# Sheet2.net
KiCad netlist of a schematic drawn in Altium Designer
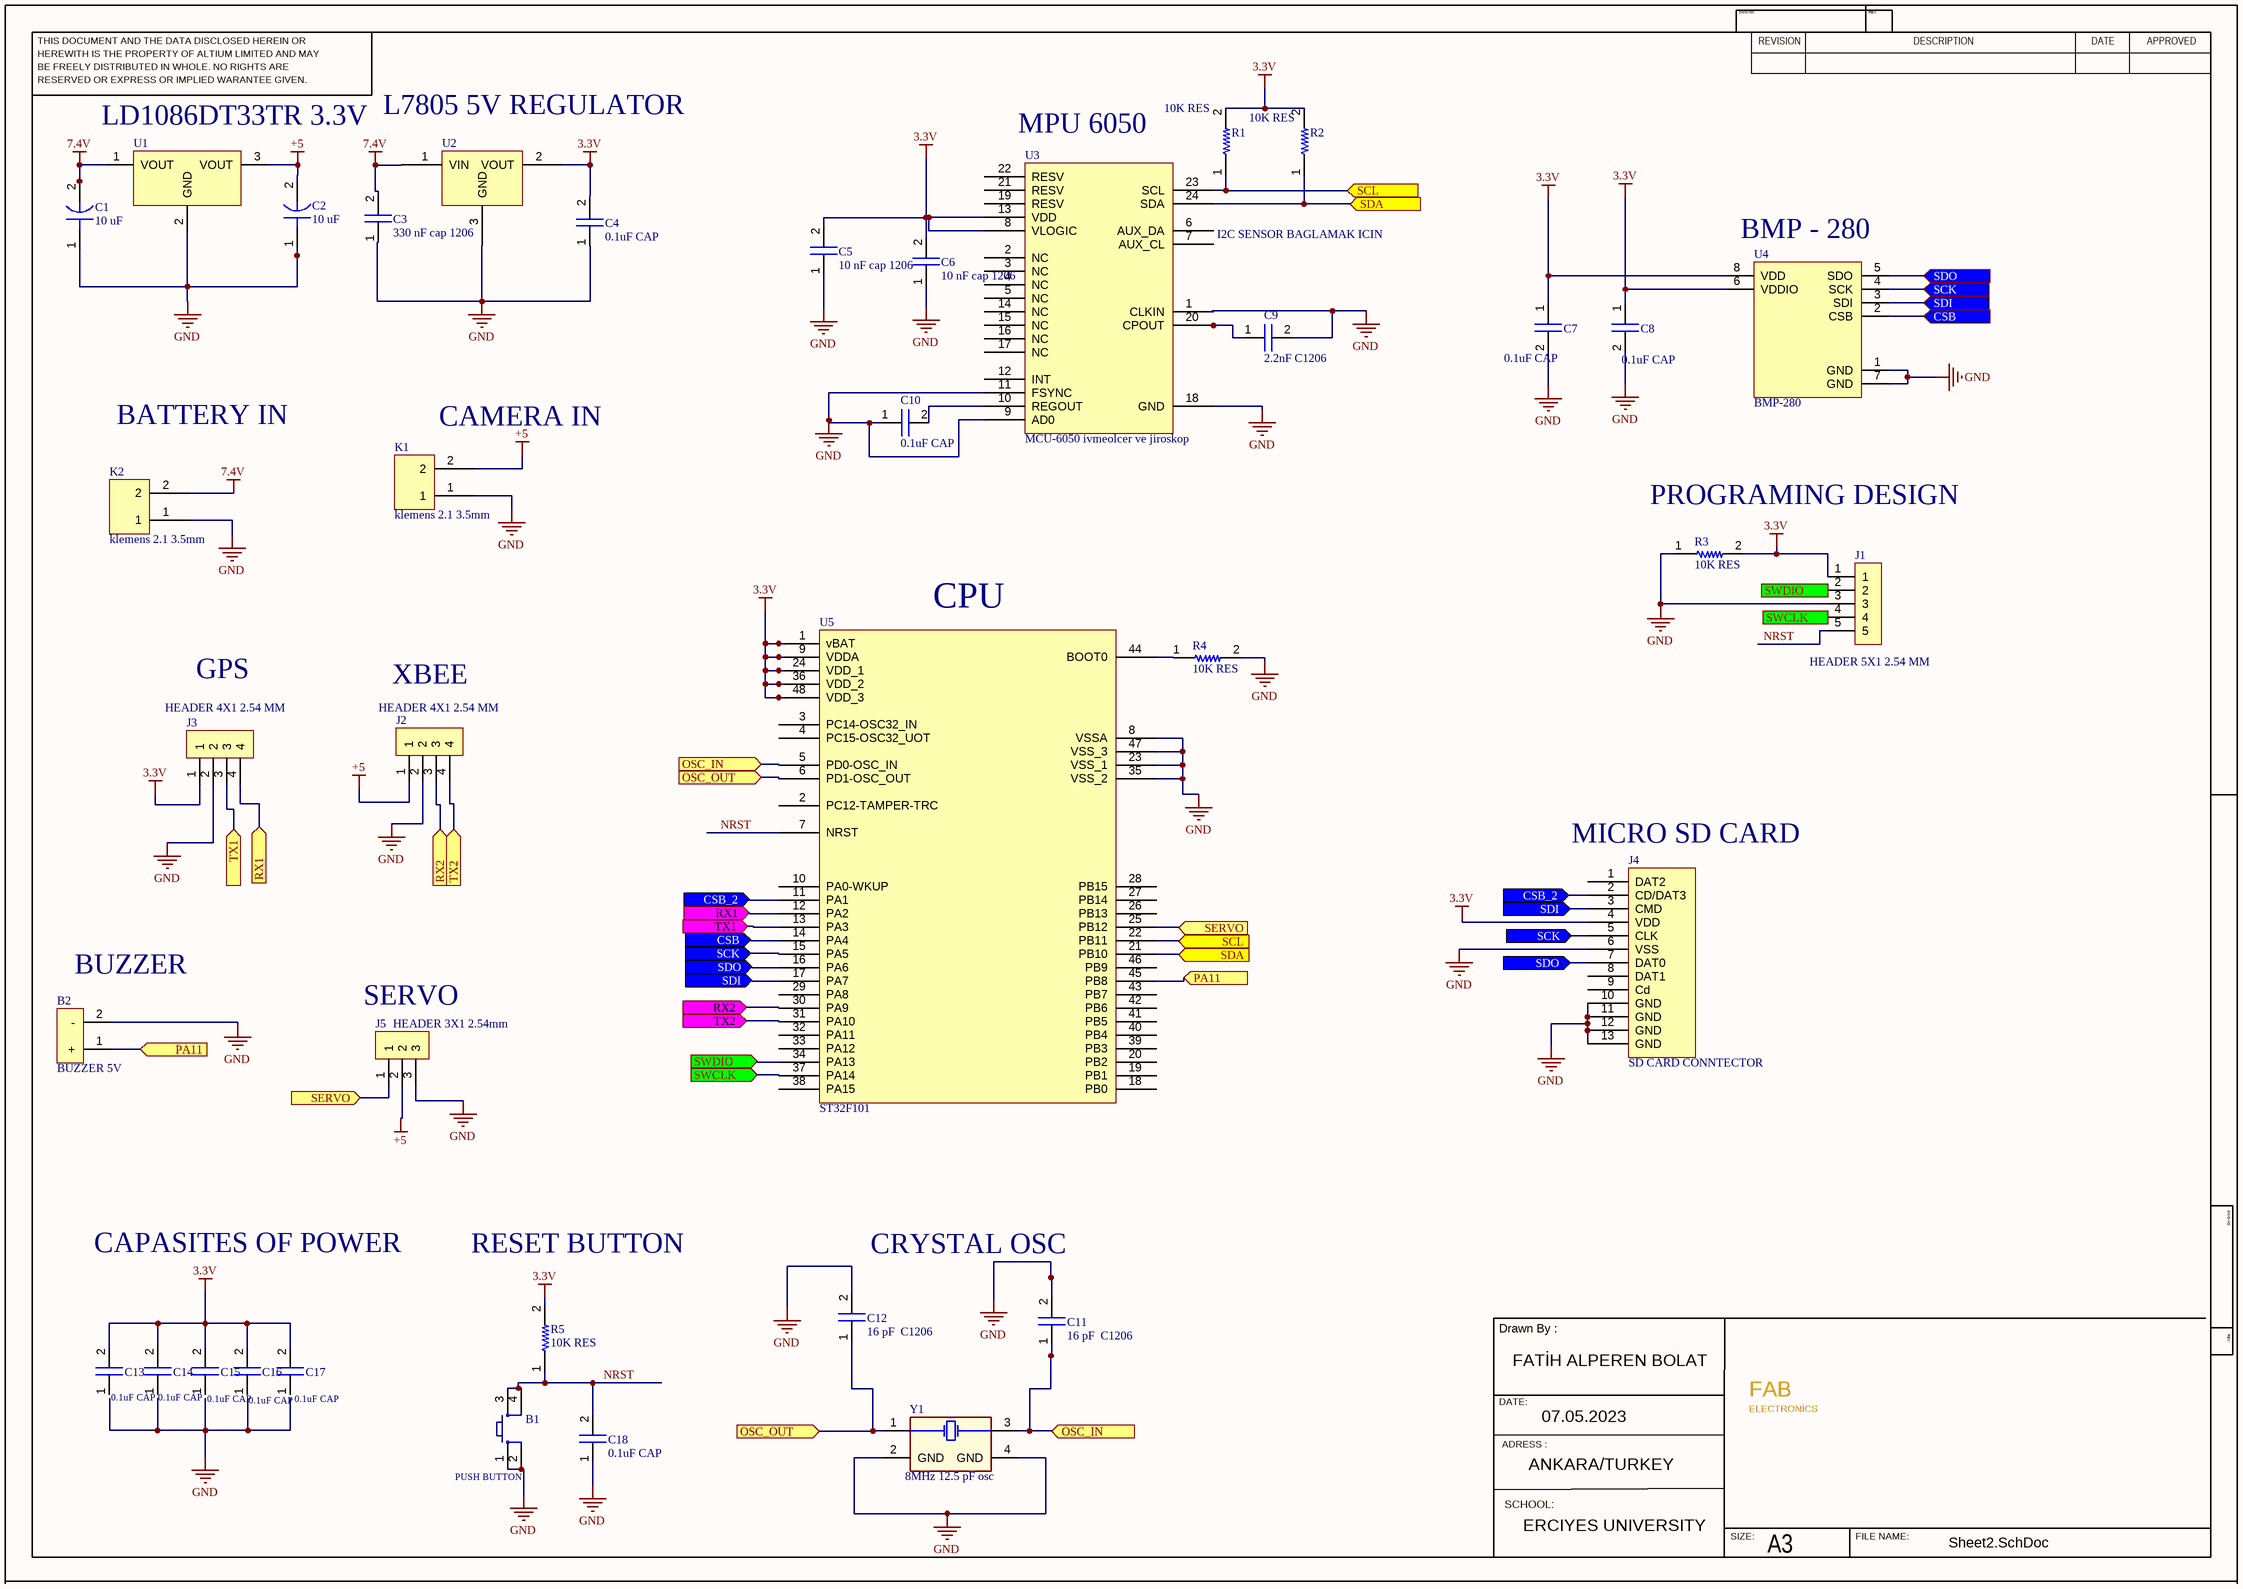
[diagram p0: Sheet2.SchDoc]

(export (version "E")
  (design (tool "Eeschema 10.0.6"))
  (components
    (comp (ref "B1")
      (value "PUSH BUTTON")
      (footprint "PUSH BUTON")
      (libsource (lib "Schlib1") (part "PUSH BUTTON"))
    )
    (comp (ref "B2")
      (value "BUZZER 5V")
      (footprint "PcbLib1:BUZZER 5V")
      (libsource (lib "Schlib1") (part "BUZZER 5V"))
    )
    (comp (ref "C1")
      (value "10 uF")
      (footprint "PcbLib1:TANTAL CAP 1206 10 nF")
      (libsource (lib "Schlib1") (part "cap1206 tantal 10 uF"))
    )
    (comp (ref "C2")
      (value "10 uF")
      (footprint "PcbLib1:TANTAL CAP 1206 10 nF")
      (libsource (lib "Schlib1") (part "cap1206 tantal 10 uF"))
    )
    (comp (ref "C3")
      (value "330 nF cap 1206")
      (footprint "CAP 1206 - 50V 0.1uF smd")
      (libsource (lib "Schlib1") (part "330 nF cap 1206"))
    )
    (comp (ref "C4")
      (value "0.1uF CAP")
      (footprint "PcbLib1:CAP 1206 - 50V 0.1uF smd")
      (libsource (lib "Schlib1") (part "0.1 uF  CAP1206"))
    )
    (comp (ref "C5")
      (value "10 nF cap 1206")
      (footprint "PcbLib1:CAP 1206 - 50V 0.1uF smd")
      (libsource (lib "Schlib1") (part "10 nF cap 1206"))
    )
    (comp (ref "C6")
      (value "10 nF cap 1206")
      (footprint "PcbLib1:CAP 1206 - 50V 0.1uF smd")
      (libsource (lib "Schlib1") (part "10 nF cap 1206"))
    )
    (comp (ref "C7")
      (value "0.1uF CAP")
      (footprint "PcbLib1:CAP 1206 - 50V 0.1uF smd")
      (libsource (lib "Schlib1") (part "0.1 uF  CAP1206"))
    )
    (comp (ref "C8")
      (value "0.1uF CAP")
      (footprint "PcbLib1:CAP 1206 - 50V 0.1uF smd")
      (libsource (lib "Schlib1") (part "0.1 uF  CAP1206"))
    )
    (comp (ref "C9")
      (value "2.2nF C1206")
      (footprint "CAP 1206 - 50V 0.1uF smd")
      (libsource (lib "Schlib1") (part "2.2nF C1206"))
    )
    (comp (ref "C10")
      (value "0.1uF CAP")
      (footprint "PcbLib1:CAP 1206 - 50V 0.1uF smd")
      (libsource (lib "Schlib1") (part "0.1 uF  CAP1206"))
    )
    (comp (ref "C11")
      (value "16 pF  C1206")
      (footprint "CAP 1206 - 50V 0.1uF smd")
      (libsource (lib "Schlib1") (part "16 pF  C1206"))
    )
    (comp (ref "C12")
      (value "16 pF  C1206")
      (footprint "CAP 1206 - 50V 0.1uF smd")
      (libsource (lib "Schlib1") (part "16 pF  C1206"))
    )
    (comp (ref "C13")
      (value "0.1uF CAP")
      (footprint "PcbLib1:CAP 1206 - 50V 0.1uF smd")
      (libsource (lib "Schlib1") (part "0.1 uF  CAP1206"))
    )
    (comp (ref "C14")
      (value "0.1uF CAP")
      (footprint "PcbLib1:CAP 1206 - 50V 0.1uF smd")
      (libsource (lib "Schlib1") (part "0.1 uF  CAP1206"))
    )
    (comp (ref "C15")
      (value "0.1uF CAP")
      (footprint "PcbLib1:CAP 1206 - 50V 0.1uF smd")
      (libsource (lib "Schlib1") (part "0.1 uF  CAP1206"))
    )
    (comp (ref "C16")
      (value "0.1uF CAP")
      (footprint "PcbLib1:CAP 1206 - 50V 0.1uF smd")
      (libsource (lib "Schlib1") (part "0.1 uF  CAP1206"))
    )
    (comp (ref "C17")
      (value "0.1uF CAP")
      (footprint "PcbLib1:CAP 1206 - 50V 0.1uF smd")
      (libsource (lib "Schlib1") (part "0.1 uF  CAP1206"))
    )
    (comp (ref "C18")
      (value "0.1uF CAP")
      (footprint "PcbLib1:CAP 1206 - 50V 0.1uF smd")
      (libsource (lib "Schlib1") (part "0.1 uF  CAP1206"))
    )
    (comp (ref "J1")
      (value "HEADER 5X1 2.54 MM")
      (footprint "PcbLib1:HEADER 5X1 2.54MM")
      (libsource (lib "Schlib1") (part "HEADER 5X1 2.54 MM"))
    )
    (comp (ref "J2")
      (value "HEADER 4X1 2.54 MM")
      (footprint "PcbLib1:HEADER 4X1 2.54 MM")
      (libsource (lib "Schlib1") (part "HEADER 4X1 2.54 MM"))
    )
    (comp (ref "J3")
      (value "HEADER 4X1 2.54 MM")
      (footprint "PcbLib1:HEADER 4X1 2.54 MM")
      (libsource (lib "Schlib1") (part "HEADER 4X1 2.54 MM"))
    )
    (comp (ref "J4")
      (value "SD CARD CONNTECTOR")
      (footprint "PcbLib1:MICRO SD CARD")
      (libsource (lib "Schlib1") (part "SD CARD"))
    )
    (comp (ref "J5")
      (value "HEADER 3X1 2.54mm")
      (footprint "PcbLib1:HEADER 2.54mm 3x1")
      (libsource (lib "Schlib1") (part "HEADER 3X1 2.54mm"))
    )
    (comp (ref "K1")
      (value "klemens 2.1 3.5mm")
      (footprint "PcbLib1:KLEMENS 1.2 3.5MM")
      (libsource (lib "Schlib1") (part "klemens 2.1 3.5mm"))
    )
    (comp (ref "K2")
      (value "klemens 2.1 3.5mm")
      (footprint "PcbLib1:KLEMENS 1.2 3.5MM")
      (libsource (lib "Schlib1") (part "klemens 2.1 3.5mm"))
    )
    (comp (ref "R1")
      (value "10K RES")
      (footprint "PcbLib1:RESISTORS")
      (libsource (lib "Schlib1") (part "10K RES"))
    )
    (comp (ref "R2")
      (value "10K RES")
      (footprint "PcbLib1:RESISTORS")
      (libsource (lib "Schlib1") (part "10K RES"))
    )
    (comp (ref "R3")
      (value "10K RES")
      (footprint "PcbLib1:RESISTORS")
      (libsource (lib "Schlib1") (part "10K RES"))
    )
    (comp (ref "R4")
      (value "10K RES")
      (footprint "PcbLib1:RESISTORS")
      (libsource (lib "Schlib1") (part "10K RES"))
    )
    (comp (ref "R5")
      (value "10K RES")
      (footprint "PcbLib1:RESISTORS")
      (libsource (lib "Schlib1") (part "10K RES"))
    )
    (comp (ref "U1")
      (value "LD1086DT33TR 3.3V")
      (footprint "PcbLib1:DPAK L7805CDT-TR")
      (libsource (lib "Schlib1") (part "LD1086DT33TR 3.3 REGULATOR"))
    )
    (comp (ref "U2")
      (value "L7805 5V REGULATOR")
      (footprint "PcbLib1:DPAK L7805CDT-TR")
      (description "L7805 5V REGULATOR SMD DPACK")
      (libsource (lib "Schlib1") (part "L7805 5V REGULATOR"))
    )
    (comp (ref "U3")
      (value "MCU-6050 ivmeolcer ve jiroskop")
      (footprint "PcbLib1:MCU-6050 ivmeolcer ve jiroskop")
      (libsource (lib "Schlib1") (part "MCU-6050 ivmeolcer ve jiroskop"))
    )
    (comp (ref "U4")
      (value "BMP-280")
      (footprint "MPU-280 BASINC SENSOR")
      (libsource (lib "Schlib1") (part "BMP-280"))
    )
    (comp (ref "U5")
      (value "ST32F101")
      (footprint "PcbLib1:LQFP48-STM32")
      (description "STM32 LQFP48 40 PİNLİ MIKROİŞLEMCİ")
      (libsource (lib "Schlib1") (part "ST32F101"))
    )
    (comp (ref "Y1")
      (value "8MHz 12.5 pF osc")
      (footprint "8 MHz 12.5 pF OSC")
      (libsource (lib "Schlib1") (part "8MHz 12.5 pF osc"))
    )
  )
  (nets
    (net (code "1") (name "+5") (class "Default")
      (node (ref "C2") (pin "2") (pinfunction "2_2") (pintype "passive"))
      (node (ref "J2") (pin "1") (pinfunction "1_1") (pintype "passive"))
      (node (ref "J5") (pin "2") (pinfunction "2_2") (pintype "passive"))
      (node (ref "K1") (pin "2") (pinfunction "2_2") (pintype "passive"))
      (node (ref "U1") (pin "3") (pinfunction "VOUT_3") (pintype "passive"))
    )
    (net (code "2") (name "/CSB") (class "Default")
      (node (ref "U4") (pin "2") (pinfunction "CSB_2") (pintype "passive"))
      (node (ref "U5") (pin "14") (pinfunction "PA4_14") (pintype "passive"))
    )
    (net (code "3") (name "/CSB_2") (class "Default")
      (node (ref "J4") (pin "2") (pinfunction "CD/DAT3_2") (pintype "passive"))
      (node (ref "U5") (pin "11") (pinfunction "PA1_11") (pintype "passive"))
    )
    (net (code "4") (name "/NRST") (class "Default")
      (node (ref "B1") (pin "3") (pinfunction "3_3") (pintype "passive"))
      (node (ref "B1") (pin "4") (pinfunction "4_4") (pintype "passive"))
      (node (ref "C18") (pin "2") (pinfunction "1_2") (pintype "passive"))
      (node (ref "J1") (pin "5") (pinfunction "5_5") (pintype "passive"))
      (node (ref "R5") (pin "1") (pinfunction "1_1") (pintype "passive"))
      (node (ref "U5") (pin "7") (pinfunction "NRST_7") (pintype "passive"))
    )
    (net (code "5") (name "/OSC_IN") (class "Default")
      (node (ref "C11") (pin "1") (pinfunction "1_1") (pintype "passive"))
      (node (ref "U5") (pin "5") (pinfunction "PD0-OSC_IN_5") (pintype "passive"))
      (node (ref "Y1") (pin "3") (pintype "passive"))
    )
    (net (code "6") (name "/OSC_OUT") (class "Default")
      (node (ref "C12") (pin "1") (pinfunction "1_1") (pintype "passive"))
      (node (ref "U5") (pin "6") (pinfunction "PD1-OSC_OUT_6") (pintype "passive"))
      (node (ref "Y1") (pin "1") (pintype "power_in"))
    )
    (net (code "7") (name "/PA11") (class "Default")
      (node (ref "B2") (pin "1") (pinfunction "+_1") (pintype "passive"))
      (node (ref "U5") (pin "45") (pinfunction "PB8_45") (pintype "passive"))
    )
    (net (code "8") (name "/RX1") (class "Default")
      (node (ref "J3") (pin "4") (pinfunction "4_4") (pintype "passive"))
      (node (ref "U5") (pin "12") (pinfunction "PA2_12") (pintype "passive"))
    )
    (net (code "9") (name "/RX2") (class "Default")
      (node (ref "J2") (pin "3") (pinfunction "3_3") (pintype "passive"))
      (node (ref "U5") (pin "30") (pinfunction "PA9_30") (pintype "passive"))
    )
    (net (code "10") (name "/SCK") (class "Default")
      (node (ref "J4") (pin "5") (pinfunction "CLK_5") (pintype "passive"))
      (node (ref "U4") (pin "4") (pinfunction "SCK_4") (pintype "passive"))
      (node (ref "U5") (pin "15") (pinfunction "PA5_15") (pintype "passive"))
    )
    (net (code "11") (name "/SCL") (class "Default")
      (node (ref "R1") (pin "1") (pinfunction "1_1") (pintype "passive"))
      (node (ref "U3") (pin "23") (pinfunction "SCL_23") (pintype "passive"))
      (node (ref "U5") (pin "22") (pinfunction "PB11_22") (pintype "passive"))
    )
    (net (code "12") (name "/SDA") (class "Default")
      (node (ref "R2") (pin "1") (pinfunction "1_1") (pintype "passive"))
      (node (ref "U3") (pin "24") (pinfunction "SDA_24") (pintype "passive"))
      (node (ref "U5") (pin "21") (pinfunction "PB10_21") (pintype "passive"))
    )
    (net (code "13") (name "/SDI") (class "Default")
      (node (ref "J4") (pin "3") (pinfunction "CMD_3") (pintype "passive"))
      (node (ref "U4") (pin "3") (pinfunction "SDI_3") (pintype "passive"))
      (node (ref "U5") (pin "17") (pinfunction "PA7_17") (pintype "passive"))
    )
    (net (code "14") (name "/SDO") (class "Default")
      (node (ref "J4") (pin "7") (pinfunction "DAT0_7") (pintype "passive"))
      (node (ref "U4") (pin "5") (pinfunction "SDO_5") (pintype "passive"))
      (node (ref "U5") (pin "16") (pinfunction "PA6_16") (pintype "passive"))
    )
    (net (code "15") (name "/SERVO") (class "Default")
      (node (ref "J5") (pin "1") (pinfunction "1_1") (pintype "passive"))
      (node (ref "U5") (pin "25") (pinfunction "PB12_25") (pintype "passive"))
    )
    (net (code "16") (name "/SWCLK") (class "Default")
      (node (ref "J1") (pin "4") (pinfunction "4_4") (pintype "passive"))
      (node (ref "U5") (pin "37") (pinfunction "PA14_37") (pintype "passive"))
    )
    (net (code "17") (name "/SWDIO") (class "Default")
      (node (ref "J1") (pin "2") (pinfunction "2_2") (pintype "passive"))
      (node (ref "U5") (pin "34") (pinfunction "PA13_34") (pintype "passive"))
    )
    (net (code "18") (name "/TX1") (class "Default")
      (node (ref "J3") (pin "3") (pinfunction "3_3") (pintype "passive"))
      (node (ref "U5") (pin "13") (pinfunction "PA3_13") (pintype "passive"))
    )
    (net (code "19") (name "/TX2") (class "Default")
      (node (ref "J2") (pin "4") (pinfunction "4_4") (pintype "passive"))
      (node (ref "U5") (pin "31") (pinfunction "PA10_31") (pintype "passive"))
    )
    (net (code "20") (name "3.3V") (class "Default")
      (node (ref "C13") (pin "2") (pinfunction "1_2") (pintype "passive"))
      (node (ref "C14") (pin "2") (pinfunction "1_2") (pintype "passive"))
      (node (ref "C15") (pin "2") (pinfunction "1_2") (pintype "passive"))
      (node (ref "C16") (pin "2") (pinfunction "1_2") (pintype "passive"))
      (node (ref "C17") (pin "2") (pinfunction "1_2") (pintype "passive"))
      (node (ref "C4") (pin "2") (pinfunction "1_2") (pintype "passive"))
      (node (ref "C5") (pin "2") (pinfunction "1_2") (pintype "passive"))
      (node (ref "C6") (pin "2") (pinfunction "1_2") (pintype "passive"))
      (node (ref "C7") (pin "1") (pinfunction "1_1") (pintype "passive"))
      (node (ref "C8") (pin "1") (pinfunction "1_1") (pintype "passive"))
      (node (ref "J1") (pin "1") (pinfunction "1_1") (pintype "passive"))
      (node (ref "J3") (pin "1") (pinfunction "1_1") (pintype "passive"))
      (node (ref "J4") (pin "4") (pinfunction "VDD_4") (pintype "passive"))
      (node (ref "R1") (pin "2") (pinfunction "2_2") (pintype "passive"))
      (node (ref "R2") (pin "2") (pinfunction "2_2") (pintype "passive"))
      (node (ref "R3") (pin "2") (pinfunction "2_2") (pintype "passive"))
      (node (ref "R5") (pin "2") (pinfunction "2_2") (pintype "passive"))
      (node (ref "U2") (pin "2") (pinfunction "VOUT_2") (pintype "passive"))
      (node (ref "U3") (pin "13") (pinfunction "VDD_13") (pintype "passive"))
      (node (ref "U3") (pin "8") (pinfunction "VLOGIC_8") (pintype "passive"))
      (node (ref "U4") (pin "6") (pinfunction "VDDIO_6") (pintype "passive"))
      (node (ref "U4") (pin "8") (pinfunction "VDD_8") (pintype "passive"))
      (node (ref "U5") (pin "1") (pinfunction "vBAT_1") (pintype "passive"))
      (node (ref "U5") (pin "24") (pinfunction "VDD_1_24") (pintype "passive"))
      (node (ref "U5") (pin "36") (pinfunction "VDD_2_36") (pintype "passive"))
      (node (ref "U5") (pin "48") (pinfunction "VDD_3_48") (pintype "passive"))
      (node (ref "U5") (pin "9") (pinfunction "VDDA_9") (pintype "passive"))
    )
    (net (code "21") (name "7.4V") (class "Default")
      (node (ref "C1") (pin "2") (pinfunction "2_2") (pintype "passive"))
      (node (ref "C3") (pin "2") (pinfunction "1_2") (pintype "passive"))
      (node (ref "K2") (pin "2") (pinfunction "2_2") (pintype "passive"))
      (node (ref "U1") (pin "1") (pinfunction "VOUT_1") (pintype "passive"))
      (node (ref "U2") (pin "1") (pinfunction "VIN_1") (pintype "passive"))
    )
    (net (code "22") (name "GND") (class "Default")
      (node (ref "B1") (pin "1") (pinfunction "1_1") (pintype "passive"))
      (node (ref "B1") (pin "2") (pinfunction "2_2") (pintype "passive"))
      (node (ref "B2") (pin "2") (pinfunction "-_2") (pintype "passive"))
      (node (ref "C1") (pin "1") (pinfunction "1_1") (pintype "passive"))
      (node (ref "C10") (pin "1") (pinfunction "1_1") (pintype "passive"))
      (node (ref "C11") (pin "2") (pinfunction "1_2") (pintype "passive"))
      (node (ref "C12") (pin "2") (pinfunction "1_2") (pintype "passive"))
      (node (ref "C18") (pin "1") (pinfunction "1_1") (pintype "passive"))
      (node (ref "C2") (pin "1") (pinfunction "1_1") (pintype "passive"))
      (node (ref "C3") (pin "1") (pinfunction "1_1") (pintype "passive"))
      (node (ref "C4") (pin "1") (pinfunction "1_1") (pintype "passive"))
      (node (ref "C5") (pin "1") (pinfunction "1_1") (pintype "passive"))
      (node (ref "C6") (pin "1") (pinfunction "1_1") (pintype "passive"))
      (node (ref "C7") (pin "2") (pinfunction "1_2") (pintype "passive"))
      (node (ref "C8") (pin "2") (pinfunction "1_2") (pintype "passive"))
      (node (ref "C9") (pin "2") (pinfunction "1_2") (pintype "passive"))
      (node (ref "J1") (pin "3") (pinfunction "3_3") (pintype "passive"))
      (node (ref "J2") (pin "2") (pinfunction "2_2") (pintype "passive"))
      (node (ref "J3") (pin "2") (pinfunction "2_2") (pintype "passive"))
      (node (ref "J4") (pin "10") (pinfunction "GND_10") (pintype "passive"))
      (node (ref "J4") (pin "11") (pinfunction "GND_11") (pintype "passive"))
      (node (ref "J4") (pin "12") (pinfunction "GND_12") (pintype "passive"))
      (node (ref "J4") (pin "13") (pinfunction "GND_13") (pintype "passive"))
      (node (ref "J4") (pin "6") (pinfunction "VSS_6") (pintype "passive"))
      (node (ref "J5") (pin "3") (pinfunction "3_3") (pintype "passive"))
      (node (ref "K1") (pin "1") (pinfunction "1_1") (pintype "passive"))
      (node (ref "K2") (pin "1") (pinfunction "1_1") (pintype "passive"))
      (node (ref "R3") (pin "1") (pinfunction "1_1") (pintype "passive"))
      (node (ref "R4") (pin "2") (pinfunction "2_2") (pintype "passive"))
      (node (ref "U1") (pin "2") (pinfunction "GND_2") (pintype "passive"))
      (node (ref "U2") (pin "3") (pinfunction "GND_3") (pintype "passive"))
      (node (ref "U3") (pin "11") (pinfunction "FSYNC_11") (pintype "passive"))
      (node (ref "U3") (pin "18") (pinfunction "GND_18") (pintype "passive"))
      (node (ref "U3") (pin "9") (pinfunction "AD0_9") (pintype "passive"))
      (node (ref "U4") (pin "1") (pinfunction "GND_1") (pintype "passive"))
      (node (ref "U4") (pin "7") (pinfunction "GND_7") (pintype "passive"))
      (node (ref "U5") (pin "23") (pinfunction "VSS_1_23") (pintype "passive"))
      (node (ref "U5") (pin "35") (pinfunction "VSS_2_35") (pintype "passive"))
      (node (ref "U5") (pin "47") (pinfunction "VSS_3_47") (pintype "passive"))
      (node (ref "U5") (pin "8") (pinfunction "VSSA_8") (pintype "passive"))
      (node (ref "Y1") (pin "2") (pinfunction "GND_2") (pintype "power_in"))
      (node (ref "Y1") (pin "4") (pinfunction "GND_4") (pintype "passive"))
    )
    (net (code "23") (name "Net-(U3-CPOUT)") (class "Default")
      (node (ref "C9") (pin "1") (pinfunction "1_1") (pintype "passive"))
      (node (ref "U3") (pin "20") (pinfunction "CPOUT_20") (pintype "passive"))
    )
    (net (code "24") (name "Net-(U3-REGOUT)") (class "Default")
      (node (ref "C10") (pin "2") (pinfunction "1_2") (pintype "passive"))
      (node (ref "U3") (pin "10") (pinfunction "REGOUT_10") (pintype "passive"))
    )
    (net (code "25") (name "Net-(U5-BOOT0)") (class "Default")
      (node (ref "R4") (pin "1") (pinfunction "1_1") (pintype "passive"))
      (node (ref "U5") (pin "44") (pinfunction "BOOT0_44") (pintype "passive"))
    )
    (net (code "26") (name "unconnected-(C13-Pad1)") (class "Default")
      (node (ref "C13") (pin "1") (pinfunction "1_1") (pintype "passive"))
    )
    (net (code "27") (name "unconnected-(C14-Pad1)") (class "Default")
      (node (ref "C14") (pin "1") (pinfunction "1_1") (pintype "passive"))
    )
    (net (code "28") (name "unconnected-(C15-Pad1)") (class "Default")
      (node (ref "C15") (pin "1") (pinfunction "1_1") (pintype "passive"))
    )
    (net (code "29") (name "unconnected-(C16-Pad1)") (class "Default")
      (node (ref "C16") (pin "1") (pinfunction "1_1") (pintype "passive"))
    )
    (net (code "30") (name "unconnected-(C17-Pad1)") (class "Default")
      (node (ref "C17") (pin "1") (pinfunction "1_1") (pintype "passive"))
    )
    (net (code "31") (name "unconnected-(J4-Cd-Pad9)") (class "Default")
      (node (ref "J4") (pin "9") (pinfunction "Cd_9") (pintype "passive"))
    )
    (net (code "32") (name "unconnected-(J4-DAT1-Pad8)") (class "Default")
      (node (ref "J4") (pin "8") (pinfunction "DAT1_8") (pintype "passive"))
    )
    (net (code "33") (name "unconnected-(J4-DAT2-Pad1)") (class "Default")
      (node (ref "J4") (pin "1") (pinfunction "DAT2_1") (pintype "passive"))
    )
    (net (code "34") (name "unconnected-(U3-AUX_CL-Pad7)") (class "Default")
      (node (ref "U3") (pin "7") (pinfunction "AUX_CL_7") (pintype "passive"))
    )
    (net (code "35") (name "unconnected-(U3-AUX_DA-Pad6)") (class "Default")
      (node (ref "U3") (pin "6") (pinfunction "AUX_DA_6") (pintype "passive"))
    )
    (net (code "36") (name "unconnected-(U3-CLKIN-Pad1)") (class "Default")
      (node (ref "U3") (pin "1") (pinfunction "CLKIN_1") (pintype "passive"))
    )
    (net (code "37") (name "unconnected-(U3-INT-Pad12)") (class "Default")
      (node (ref "U3") (pin "12") (pinfunction "INT_12") (pintype "passive"))
    )
    (net (code "38") (name "unconnected-(U3-NC-Pad2)") (class "Default")
      (node (ref "U3") (pin "2") (pinfunction "NC_2") (pintype "passive"))
    )
    (net (code "39") (name "unconnected-(U3-NC-Pad3)") (class "Default")
      (node (ref "U3") (pin "3") (pinfunction "NC_3") (pintype "passive"))
    )
    (net (code "40") (name "unconnected-(U3-NC-Pad4)") (class "Default")
      (node (ref "U3") (pin "4") (pinfunction "NC_4") (pintype "passive"))
    )
    (net (code "41") (name "unconnected-(U3-NC-Pad5)") (class "Default")
      (node (ref "U3") (pin "5") (pinfunction "NC_5") (pintype "passive"))
    )
    (net (code "42") (name "unconnected-(U3-NC-Pad14)") (class "Default")
      (node (ref "U3") (pin "14") (pinfunction "NC_14") (pintype "passive"))
    )
    (net (code "43") (name "unconnected-(U3-NC-Pad15)") (class "Default")
      (node (ref "U3") (pin "15") (pinfunction "NC_15") (pintype "passive"))
    )
    (net (code "44") (name "unconnected-(U3-NC-Pad16)") (class "Default")
      (node (ref "U3") (pin "16") (pinfunction "NC_16") (pintype "passive"))
    )
    (net (code "45") (name "unconnected-(U3-NC-Pad17)") (class "Default")
      (node (ref "U3") (pin "17") (pinfunction "NC_17") (pintype "passive"))
    )
    (net (code "46") (name "unconnected-(U3-RESV-Pad19)") (class "Default")
      (node (ref "U3") (pin "19") (pinfunction "RESV_19") (pintype "passive"))
    )
    (net (code "47") (name "unconnected-(U3-RESV-Pad21)") (class "Default")
      (node (ref "U3") (pin "21") (pinfunction "RESV_21") (pintype "passive"))
    )
    (net (code "48") (name "unconnected-(U3-RESV-Pad22)") (class "Default")
      (node (ref "U3") (pin "22") (pinfunction "RESV_22") (pintype "passive"))
    )
    (net (code "49") (name "unconnected-(U5-PA0-WKUP-Pad10)") (class "Default")
      (node (ref "U5") (pin "10") (pinfunction "PA0-WKUP_10") (pintype "passive"))
    )
    (net (code "50") (name "unconnected-(U5-PA8-Pad29)") (class "Default")
      (node (ref "U5") (pin "29") (pinfunction "PA8_29") (pintype "passive"))
    )
    (net (code "51") (name "unconnected-(U5-PA11-Pad32)") (class "Default")
      (node (ref "U5") (pin "32") (pinfunction "PA11_32") (pintype "passive"))
    )
    (net (code "52") (name "unconnected-(U5-PA12-Pad33)") (class "Default")
      (node (ref "U5") (pin "33") (pinfunction "PA12_33") (pintype "passive"))
    )
    (net (code "53") (name "unconnected-(U5-PA15-Pad38)") (class "Default")
      (node (ref "U5") (pin "38") (pinfunction "PA15_38") (pintype "passive"))
    )
    (net (code "54") (name "unconnected-(U5-PB0-Pad18)") (class "Default")
      (node (ref "U5") (pin "18") (pinfunction "PB0_18") (pintype "passive"))
    )
    (net (code "55") (name "unconnected-(U5-PB1-Pad19)") (class "Default")
      (node (ref "U5") (pin "19") (pinfunction "PB1_19") (pintype "passive"))
    )
    (net (code "56") (name "unconnected-(U5-PB2-Pad20)") (class "Default")
      (node (ref "U5") (pin "20") (pinfunction "PB2_20") (pintype "passive"))
    )
    (net (code "57") (name "unconnected-(U5-PB3-Pad39)") (class "Default")
      (node (ref "U5") (pin "39") (pinfunction "PB3_39") (pintype "passive"))
    )
    (net (code "58") (name "unconnected-(U5-PB4-Pad40)") (class "Default")
      (node (ref "U5") (pin "40") (pinfunction "PB4_40") (pintype "passive"))
    )
    (net (code "59") (name "unconnected-(U5-PB5-Pad41)") (class "Default")
      (node (ref "U5") (pin "41") (pinfunction "PB5_41") (pintype "passive"))
    )
    (net (code "60") (name "unconnected-(U5-PB6-Pad42)") (class "Default")
      (node (ref "U5") (pin "42") (pinfunction "PB6_42") (pintype "passive"))
    )
    (net (code "61") (name "unconnected-(U5-PB7-Pad43)") (class "Default")
      (node (ref "U5") (pin "43") (pinfunction "PB7_43") (pintype "passive"))
    )
    (net (code "62") (name "unconnected-(U5-PB9-Pad46)") (class "Default")
      (node (ref "U5") (pin "46") (pinfunction "PB9_46") (pintype "passive"))
    )
    (net (code "63") (name "unconnected-(U5-PB13-Pad26)") (class "Default")
      (node (ref "U5") (pin "26") (pinfunction "PB13_26") (pintype "passive"))
    )
    (net (code "64") (name "unconnected-(U5-PB14-Pad27)") (class "Default")
      (node (ref "U5") (pin "27") (pinfunction "PB14_27") (pintype "passive"))
    )
    (net (code "65") (name "unconnected-(U5-PB15-Pad28)") (class "Default")
      (node (ref "U5") (pin "28") (pinfunction "PB15_28") (pintype "passive"))
    )
    (net (code "66") (name "unconnected-(U5-PC12-TAMPER-TRC-Pad2)") (class "Default")
      (node (ref "U5") (pin "2") (pinfunction "PC12-TAMPER-TRC_2") (pintype "passive"))
    )
    (net (code "67") (name "unconnected-(U5-PC14-OSC32_IN-Pad3)") (class "Default")
      (node (ref "U5") (pin "3") (pinfunction "PC14-OSC32_IN_3") (pintype "passive"))
    )
    (net (code "68") (name "unconnected-(U5-PC15-OSC32_UOT-Pad4)") (class "Default")
      (node (ref "U5") (pin "4") (pinfunction "PC15-OSC32_UOT_4") (pintype "passive"))
    )
  )
)
